# Sheet1.net
KiCad netlist of a schematic drawn in Altium Designer
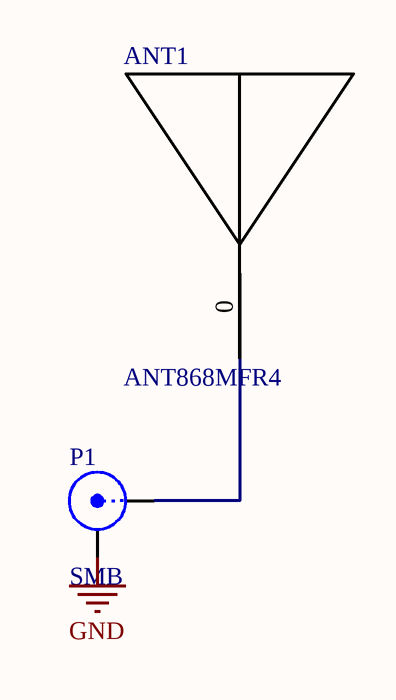
[diagram p0: Sheet1.SchDoc]

(export (version "E")
  (design (tool "Eeschema 10.0.6"))
  (components
    (comp (ref "ANT1")
      (value "ANT868MFR4")
      (footprint "ANT868MFR4")
      (libsource (lib "AntLib") (part "ANT868MFR4"))
    )
    (comp (ref "P1")
      (value "SMB")
      (footprint "SMB_V-RJ45")
      (description "SMB Straight Connector")
      (fields (field (name "PUBLISHER") "Altium Limited"))
      (libsource (lib "Miscellaneous Connectors") (part "SMB"))
    )
  )
  (nets
    (net (code "1") (name "GND") (class "Default")
      (node (ref "P1") (pin "2") (pinfunction "Y_2") (pintype "passive"))
    )
    (net (code "2") (name "Net-(P1-X)") (class "Default")
      (node (ref "ANT1") (pin "0") (pinfunction "0_0") (pintype "passive"))
      (node (ref "P1") (pin "1") (pinfunction "X_1") (pintype "passive"))
    )
  )
)
